# LOAD.net
KiCad netlist of a schematic drawn in Altium Designer
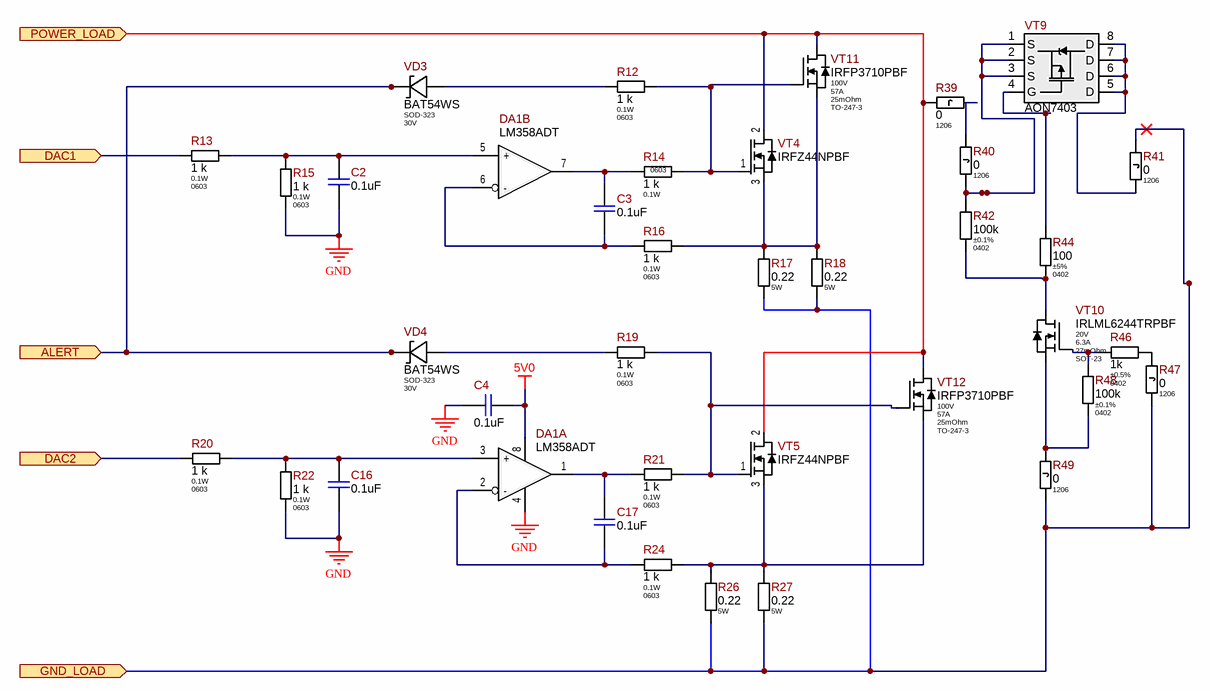
[diagram p0: LOAD.SchDoc]

(export (version "E")
  (design (tool "Eeschema 10.0.6"))
  (components
    (comp (ref "C2")
      (value "0.1uF")
      (footprint "C0603(1608)")
      (description "CAP CER 0.1UF 50V X7R 0603")
      (fields (field (name "PART NUMBER") "0.1uF  50V C0603") (field (name "TOLERANCE") "±10%"))
      (libsource (lib "Database") (part "Capacitor_Ceramic"))
    )
    (comp (ref "C3")
      (value "0.1uF")
      (footprint "C0603(1608)")
      (description "CAP CER 0.1UF 50V X7R 0603")
      (fields (field (name "PART NUMBER") "0.1uF  50V C0603") (field (name "TOLERANCE") "±10%"))
      (libsource (lib "Database") (part "Capacitor_Ceramic"))
    )
    (comp (ref "C4")
      (value "0.1uF")
      (footprint "C0603(1608)")
      (description "CAP CER 0.1UF 50V X7R 0603")
      (fields (field (name "PART NUMBER") "0.1uF  50V C0603") (field (name "TOLERANCE") "±10%"))
      (libsource (lib "Database") (part "Capacitor_Ceramic"))
    )
    (comp (ref "C16")
      (value "0.1uF")
      (footprint "C0603(1608)")
      (description "CAP CER 0.1UF 50V X7R 0603")
      (fields (field (name "PART NUMBER") "0.1uF  50V C0603") (field (name "TOLERANCE") "±10%"))
      (libsource (lib "Database") (part "Capacitor_Ceramic"))
    )
    (comp (ref "C17")
      (value "0.1uF")
      (footprint "C0603(1608)")
      (description "CAP CER 0.1UF 50V X7R 0603")
      (fields (field (name "PART NUMBER") "0.1uF  50V C0603") (field (name "TOLERANCE") "±10%"))
      (libsource (lib "Database") (part "Capacitor_Ceramic"))
    )
    (comp (ref "DA1")
      (value "LM358ADT")
      (footprint "SOIC8")
      (description "IC OPAMP GP 2 CIRCUIT 8SOIC  1.1 MHz   3V...30V")
      (fields (field (name "MANUFACTURER") "Texas Instruments"))
      (libsource (lib "Database") (part "AMP8"))
    )
    (comp (ref "R12")
      (value "1 k")
      (footprint "R0603")
      (description "RES SMD 1 k OHM  ±1% 1/10W 0603")
      (fields
        (field (name "POWER RATING") "0.1W")
        (field (name "PACKAGE/CASE") "0603")
        (field (name "PART NUMBER") "1 k  R0603")
        (field (name "TOLERANCE") "±1%")
      )
      (libsource (lib "Database") (part "R0603"))
    )
    (comp (ref "R13")
      (value "1 k")
      (footprint "R0603")
      (description "RES SMD 1 k OHM  ±1% 1/10W 0603")
      (fields
        (field (name "POWER RATING") "0.1W")
        (field (name "PACKAGE/CASE") "0603")
        (field (name "PART NUMBER") "1 k  R0603")
        (field (name "TOLERANCE") "±1%")
      )
      (libsource (lib "Database") (part "R0603"))
    )
    (comp (ref "R14")
      (value "1 k")
      (footprint "R0603")
      (description "RES SMD 1 k OHM  ±1% 1/10W 0603")
      (fields
        (field (name "POWER RATING") "0.1W")
        (field (name "PACKAGE/CASE") "0603")
        (field (name "PART NUMBER") "1 k  R0603")
        (field (name "TOLERANCE") "±1%")
      )
      (libsource (lib "Database") (part "R0603"))
    )
    (comp (ref "R15")
      (value "1 k")
      (footprint "R0603")
      (description "RES SMD 1 k OHM  ±1% 1/10W 0603")
      (fields
        (field (name "POWER RATING") "0.1W")
        (field (name "PACKAGE/CASE") "0603")
        (field (name "PART NUMBER") "1 k  R0603")
        (field (name "TOLERANCE") "±1%")
      )
      (libsource (lib "Database") (part "R0603"))
    )
    (comp (ref "R16")
      (value "1 k")
      (footprint "R0603")
      (description "RES SMD 1 k OHM  ±1% 1/10W 0603")
      (fields
        (field (name "POWER RATING") "0.1W")
        (field (name "PACKAGE/CASE") "0603")
        (field (name "PART NUMBER") "1 k  R0603")
        (field (name "TOLERANCE") "±1%")
      )
      (libsource (lib "Database") (part "R0603"))
    )
    (comp (ref "R17")
      (value "0.22")
      (footprint "R5W")
      (description "Resistror 47 OHM  ±10% AXIAL  9.00mm x 22.00mm")
      (fields
        (field (name "POWER RATING") "5W")
        (field (name "PART NUMBER") "47  RES_5W")
        (field (name "TOLERANCE") "±10%")
      )
      (libsource (lib "Database") (part "RES_5W"))
    )
    (comp (ref "R18")
      (value "0.22")
      (footprint "R5W")
      (description "Resistror 47 OHM  ±10% AXIAL  9.00mm x 22.00mm")
      (fields
        (field (name "POWER RATING") "5W")
        (field (name "PART NUMBER") "47  RES_5W")
        (field (name "TOLERANCE") "±10%")
      )
      (libsource (lib "Database") (part "RES_5W"))
    )
    (comp (ref "R19")
      (value "1 k")
      (footprint "R0603")
      (description "RES SMD 1 k OHM  ±1% 1/10W 0603")
      (fields
        (field (name "POWER RATING") "0.1W")
        (field (name "PACKAGE/CASE") "0603")
        (field (name "PART NUMBER") "1 k  R0603")
        (field (name "TOLERANCE") "±1%")
      )
      (libsource (lib "Database") (part "R0603"))
    )
    (comp (ref "R20")
      (value "1 k")
      (footprint "R0603")
      (description "RES SMD 1 k OHM  ±1% 1/10W 0603")
      (fields
        (field (name "POWER RATING") "0.1W")
        (field (name "PACKAGE/CASE") "0603")
        (field (name "PART NUMBER") "1 k  R0603")
        (field (name "TOLERANCE") "±1%")
      )
      (libsource (lib "Database") (part "R0603"))
    )
    (comp (ref "R21")
      (value "1 k")
      (footprint "R0603")
      (description "RES SMD 1 k OHM  ±1% 1/10W 0603")
      (fields
        (field (name "POWER RATING") "0.1W")
        (field (name "PACKAGE/CASE") "0603")
        (field (name "PART NUMBER") "1 k  R0603")
        (field (name "TOLERANCE") "±1%")
      )
      (libsource (lib "Database") (part "R0603"))
    )
    (comp (ref "R22")
      (value "1 k")
      (footprint "R0603")
      (description "RES SMD 1 k OHM  ±1% 1/10W 0603")
      (fields
        (field (name "POWER RATING") "0.1W")
        (field (name "PACKAGE/CASE") "0603")
        (field (name "PART NUMBER") "1 k  R0603")
        (field (name "TOLERANCE") "±1%")
      )
      (libsource (lib "Database") (part "R0603"))
    )
    (comp (ref "R24")
      (value "1 k")
      (footprint "R0603")
      (description "RES SMD 1 k OHM  ±1% 1/10W 0603")
      (fields
        (field (name "POWER RATING") "0.1W")
        (field (name "PACKAGE/CASE") "0603")
        (field (name "PART NUMBER") "1 k  R0603")
        (field (name "TOLERANCE") "±1%")
      )
      (libsource (lib "Database") (part "R0603"))
    )
    (comp (ref "R26")
      (value "0.22")
      (footprint "R5W")
      (description "Resistror 47 OHM  ±10% AXIAL  9.00mm x 22.00mm")
      (fields
        (field (name "POWER RATING") "5W")
        (field (name "PART NUMBER") "47  RES_5W")
        (field (name "TOLERANCE") "±10%")
      )
      (libsource (lib "Database") (part "RES_5W"))
    )
    (comp (ref "R27")
      (value "0.22")
      (footprint "R5W")
      (description "Resistror 47 OHM  ±10% AXIAL  9.00mm x 22.00mm")
      (fields
        (field (name "POWER RATING") "5W")
        (field (name "PART NUMBER") "47  RES_5W")
        (field (name "TOLERANCE") "±10%")
      )
      (libsource (lib "Database") (part "RES_5W"))
    )
    (comp (ref "R39")
      (value "0")
      (footprint "R_ANY_CHIP_1206_MED")
      (description "0 Ohms Jumper, 1/2W 1206 Thick Film Resistor")
      (fields
        (field (name "TOLERANCE") "0.5%")
        (field (name "PACKAGE") "1206")
        (field (name "PART NUMBER") "RCS12060000Z0EA")
      )
      (libsource (lib "AjaxLibrary") (part "Resistor-J"))
    )
    (comp (ref "R40")
      (value "0")
      (footprint "R_ANY_CHIP_1206_MED")
      (description "0 Ohms Jumper, 1/2W 1206 Thick Film Resistor")
      (fields
        (field (name "TOLERANCE") "0.5%")
        (field (name "PACKAGE") "1206")
        (field (name "PART NUMBER") "RCS12060000Z0EA")
      )
      (libsource (lib "AjaxLibrary") (part "Resistor-J"))
    )
    (comp (ref "R41")
      (value "0")
      (footprint "R_ANY_CHIP_1206_MED")
      (description "0 Ohms Jumper, 1/2W 1206 Thick Film Resistor")
      (fields
        (field (name "TOLERANCE") "0.5%")
        (field (name "PACKAGE") "1206")
        (field (name "PART NUMBER") "RCS12060000Z0EA")
      )
      (libsource (lib "AjaxLibrary") (part "Resistor-J"))
    )
    (comp (ref "R42")
      (value "100k")
      (footprint "R_ANY_CHIP_0402_MED")
      (description "100 kOhms ±0.1%, 1/16W 0402 Thin Film Resistor")
      (fields
        (field (name "TOLERANCE") "±0.1%")
        (field (name "PACKAGE") "0402")
        (field (name "PART NUMBER") "WF04U1003BTL")
        (field (name "MANUFACTURER") "Walsin Technology Corporation")
      )
      (libsource (lib "AjaxLibrary") (part "Resistor"))
    )
    (comp (ref "R44")
      (value "100")
      (footprint "R_ANY_CHIP_0402_MED")
      (description "100 Ohms ±5% 1/16W 0402 Thick Film Resistor")
      (fields
        (field (name "TOLERANCE") "±5%")
        (field (name "PACKAGE") "0402")
        (field (name "PART NUMBER") "RC0402JR-07100RL")
        (field (name "MANUFACTURER") "Yageo")
      )
      (libsource (lib "AjaxLibrary") (part "Resistor"))
    )
    (comp (ref "R46")
      (value "1k")
      (footprint "R_ANY_CHIP_0402_MED")
      (description "1 kOhms ±0.5% 1/16W 0402 Thick Film Resistor")
      (fields
        (field (name "TOLERANCE") "±0.5%")
        (field (name "PACKAGE") "0402")
        (field (name "PART NUMBER") "RC0402DR-071KL")
        (field (name "MANUFACTURER") "Yageo")
      )
      (libsource (lib "AjaxLibrary") (part "Resistor"))
    )
    (comp (ref "R47")
      (value "0")
      (footprint "R_ANY_CHIP_1206_MED")
      (description "0 Ohms Jumper, 1/2W 1206 Thick Film Resistor")
      (fields
        (field (name "TOLERANCE") "0.5%")
        (field (name "PACKAGE") "1206")
        (field (name "PART NUMBER") "RCS12060000Z0EA")
      )
      (libsource (lib "AjaxLibrary") (part "Resistor-J"))
    )
    (comp (ref "R48")
      (value "100k")
      (footprint "R_ANY_CHIP_0402_MED")
      (description "100 kOhms ±0.1%, 1/16W 0402 Thin Film Resistor")
      (fields
        (field (name "TOLERANCE") "±0.1%")
        (field (name "PACKAGE") "0402")
        (field (name "PART NUMBER") "WF04U1003BTL")
        (field (name "MANUFACTURER") "Walsin Technology Corporation")
      )
      (libsource (lib "AjaxLibrary") (part "Resistor"))
    )
    (comp (ref "R49")
      (value "0")
      (footprint "R_ANY_CHIP_1206_MED")
      (description "0 Ohms Jumper, 1/2W 1206 Thick Film Resistor")
      (fields
        (field (name "TOLERANCE") "0.5%")
        (field (name "PACKAGE") "1206")
        (field (name "PART NUMBER") "RCS12060000Z0EA")
      )
      (libsource (lib "AjaxLibrary") (part "Resistor-J"))
    )
    (comp (ref "VD3")
      (value "BAT54WS")
      (footprint "SOD-323_MED")
      (description "Diode Schottky 30V 100mA, Fast Recovery 5ns, Low Leakage 2uA, SOD-323")
      (fields
        (field (name "PART NUMBER") "BAT54WS-7-F")
        (field (name "MANUFACTURER") "Diodes Incorporated")
        (field (name "PACKAGE") "SOD-323")
        (field (name "VOLTAGE") "30V")
      )
      (libsource (lib "AjaxLibrary") (part "Diode-Schottky"))
    )
    (comp (ref "VD4")
      (value "BAT54WS")
      (footprint "SOD-323_MED")
      (description "Diode Schottky 30V 100mA, Fast Recovery 5ns, Low Leakage 2uA, SOD-323")
      (fields
        (field (name "PART NUMBER") "BAT54WS-7-F")
        (field (name "MANUFACTURER") "Diodes Incorporated")
        (field (name "PACKAGE") "SOD-323")
        (field (name "VOLTAGE") "30V")
      )
      (libsource (lib "AjaxLibrary") (part "Diode-Schottky"))
    )
    (comp (ref "VT4")
      (value "IRFZ44NPBF")
      (footprint "TO-220")
      (description "MOSFET N-CH 55V 49A TO220AB")
      (fields (field (name "MANUFACTURER") "Infineon Technologies"))
      (libsource (lib "Database") (part "IRFZ44"))
    )
    (comp (ref "VT5")
      (value "IRFZ44NPBF")
      (footprint "TO-220")
      (description "MOSFET N-CH 55V 49A TO220AB")
      (fields (field (name "MANUFACTURER") "Infineon Technologies"))
      (libsource (lib "Database") (part "IRFZ44"))
    )
    (comp (ref "VT9")
      (value "AON7403")
      (footprint "DFN3X3")
      (description "P-Channel 30 V 11A (Ta), 29A (Tc) 3.1W (Ta), 25W (Tc) Surface Mount 8-DFN-EP (3x3)")
      (fields
        (field (name "PART NUMBER") "AON7403")
        (field (name "MANUFACTURER") "Alpha & Omega Semiconductor Inc.")
      )
      (libsource (lib "Database") (part "AON7403"))
    )
    (comp (ref "VT10")
      (value "IRLML6244")
      (footprint "SOT-23_MED")
      (description "20V, 6.3A max N-Channel HEXFET MOSFET, 21mOhm @ Vgs = 4.5V")
      (fields
        (field (name "PART NUMBER") "IRLML6244TRPBF")
        (field (name "VDS") "20V")
        (field (name "ID") "6.3A")
        (field (name "RDS") "27mOhm")
        (field (name "PACKAGE") "SOT-23")
        (field (name "MANUFACTURER") "Infineon Technologies")
      )
      (libsource (lib "AjaxLibrary") (part "MOSFET-N-Channel"))
    )
    (comp (ref "VT11")
      (value "IRFP3710PBF")
      (footprint "TO-247-3")
      (description "100V, 57A max N-Channel HEXFET Power MOSFET, 25mOhm @ Vgs = 10V")
      (fields
        (field (name "PART NUMBER") "IRFP3710PBF")
        (field (name "VDS") "100V")
        (field (name "ID") "57A")
        (field (name "RDS") "25mOhm")
        (field (name "PACKAGE") "TO-247-3")
        (field (name "MANUFACTURER") "Infineon Technologies")
      )
      (libsource (lib "AjaxLibrary") (part "MOSFET-N-Channel-(TO-247)"))
    )
    (comp (ref "VT12")
      (value "IRFP3710PBF")
      (footprint "TO-247-3")
      (description "100V, 57A max N-Channel HEXFET Power MOSFET, 25mOhm @ Vgs = 10V")
      (fields
        (field (name "PART NUMBER") "IRFP3710PBF")
        (field (name "VDS") "100V")
        (field (name "ID") "57A")
        (field (name "RDS") "25mOhm")
        (field (name "PACKAGE") "TO-247-3")
        (field (name "MANUFACTURER") "Infineon Technologies")
      )
      (libsource (lib "AjaxLibrary") (part "MOSFET-N-Channel-(TO-247)"))
    )
  )
  (nets
    (net (code "1") (name "/ALERT") (class "Default")
      (node (ref "VD3") (pin "CA") (pintype "passive"))
      (node (ref "VD4") (pin "CA") (pintype "passive"))
    )
    (net (code "2") (name "/DAC1") (class "Default")
      (node (ref "R13") (pin "1") (pinfunction "1_1") (pintype "passive"))
    )
    (net (code "3") (name "/DAC2") (class "Default")
      (node (ref "R20") (pin "1") (pinfunction "1_1") (pintype "passive"))
    )
    (net (code "4") (name "/GND_LOAD") (class "Default")
      (node (ref "R17") (pin "1") (pinfunction "1_1") (pintype "passive"))
      (node (ref "R18") (pin "1") (pinfunction "1_1") (pintype "passive"))
      (node (ref "R26") (pin "1") (pinfunction "1_1") (pintype "passive"))
      (node (ref "R27") (pin "1") (pinfunction "1_1") (pintype "passive"))
      (node (ref "R41") (pin "1") (pintype "passive"))
      (node (ref "R47") (pin "2") (pintype "passive"))
      (node (ref "R49") (pin "2") (pintype "passive"))
    )
    (net (code "5") (name "/POWER_LOAD") (class "Default")
      (node (ref "R39") (pin "1") (pintype "passive"))
      (node (ref "VT11") (pin "2") (pinfunction "D_2") (pintype "passive"))
      (node (ref "VT12") (pin "2") (pinfunction "D_2") (pintype "passive"))
      (node (ref "VT4") (pin "2") (pinfunction "D_2") (pintype "passive"))
      (node (ref "VT5") (pin "2") (pinfunction "D_2") (pintype "passive"))
    )
    (net (code "6") (name "5V0") (class "Default")
      (node (ref "C4") (pin "1") (pinfunction "1_1") (pintype "passive"))
      (node (ref "DA1") (pin "8") (pinfunction "V+_8") (pintype "passive"))
    )
    (net (code "7") (name "GND") (class "Default")
      (node (ref "C16") (pin "2") (pinfunction "2_2") (pintype "passive"))
      (node (ref "C2") (pin "2") (pinfunction "2_2") (pintype "passive"))
      (node (ref "C4") (pin "2") (pinfunction "2_2") (pintype "passive"))
      (node (ref "DA1") (pin "4") (pinfunction "V-_4") (pintype "passive"))
      (node (ref "R15") (pin "1") (pinfunction "1_1") (pintype "passive"))
      (node (ref "R22") (pin "1") (pinfunction "1_1") (pintype "passive"))
    )
    (net (code "8") (name "Net-(DA1A-+)") (class "Default")
      (node (ref "C16") (pin "1") (pinfunction "1_1") (pintype "passive"))
      (node (ref "DA1") (pin "3") (pinfunction "+_3") (pintype "passive"))
      (node (ref "R20") (pin "2") (pinfunction "2_2") (pintype "passive"))
      (node (ref "R22") (pin "2") (pinfunction "2_2") (pintype "passive"))
    )
    (net (code "9") (name "Net-(DA1A--)") (class "Default")
      (node (ref "C17") (pin "2") (pinfunction "2_2") (pintype "passive"))
      (node (ref "DA1") (pin "2") (pinfunction "-_2") (pintype "passive"))
      (node (ref "R24") (pin "1") (pinfunction "1_1") (pintype "passive"))
    )
    (net (code "10") (name "Net-(DA1A-Out)") (class "Default")
      (node (ref "C17") (pin "1") (pinfunction "1_1") (pintype "passive"))
      (node (ref "DA1") (pin "1") (pinfunction "Out_1") (pintype "passive"))
      (node (ref "R21") (pin "1") (pinfunction "1_1") (pintype "passive"))
    )
    (net (code "11") (name "Net-(DA1B-+)") (class "Default")
      (node (ref "C2") (pin "1") (pinfunction "1_1") (pintype "passive"))
      (node (ref "DA1") (pin "5") (pinfunction "+_5") (pintype "passive"))
      (node (ref "R13") (pin "2") (pinfunction "2_2") (pintype "passive"))
      (node (ref "R15") (pin "2") (pinfunction "2_2") (pintype "passive"))
    )
    (net (code "12") (name "Net-(DA1B--)") (class "Default")
      (node (ref "C3") (pin "2") (pinfunction "2_2") (pintype "passive"))
      (node (ref "DA1") (pin "6") (pinfunction "-_6") (pintype "passive"))
      (node (ref "R16") (pin "1") (pinfunction "1_1") (pintype "passive"))
    )
    (net (code "13") (name "Net-(DA1B-Out)") (class "Default")
      (node (ref "C3") (pin "1") (pinfunction "1_1") (pintype "passive"))
      (node (ref "DA1") (pin "7") (pinfunction "Out_7") (pintype "passive"))
      (node (ref "R14") (pin "1") (pinfunction "1_1") (pintype "passive"))
    )
    (net (code "14") (name "Net-(R12-Pad1)") (class "Default")
      (node (ref "R12") (pin "1") (pinfunction "1_1") (pintype "passive"))
      (node (ref "VD3") (pin "AN") (pintype "passive"))
    )
    (net (code "15") (name "Net-(R19-Pad1)") (class "Default")
      (node (ref "R19") (pin "1") (pinfunction "1_1") (pintype "passive"))
      (node (ref "VD4") (pin "AN") (pintype "passive"))
    )
    (net (code "16") (name "Net-(R39-Pad2)") (class "Default")
      (node (ref "R39") (pin "2") (pintype "passive"))
      (node (ref "R40") (pin "1") (pintype "passive"))
    )
    (net (code "17") (name "Net-(R40-Pad2)") (class "Default")
      (node (ref "R40") (pin "2") (pintype "passive"))
      (node (ref "R42") (pin "1") (pintype "passive"))
      (node (ref "VT9") (pin "1") (pinfunction "S_1") (pintype "passive"))
      (node (ref "VT9") (pin "2") (pinfunction "S_2") (pintype "passive"))
      (node (ref "VT9") (pin "3") (pinfunction "S_3") (pintype "passive"))
    )
    (net (code "18") (name "Net-(R41-Pad2)") (class "Default")
      (node (ref "R41") (pin "2") (pintype "passive"))
      (node (ref "VT9") (pin "5") (pinfunction "D_5") (pintype "passive"))
      (node (ref "VT9") (pin "6") (pinfunction "D_6") (pintype "passive"))
      (node (ref "VT9") (pin "7") (pinfunction "D_7") (pintype "passive"))
      (node (ref "VT9") (pin "8") (pinfunction "D_8") (pintype "passive"))
    )
    (net (code "19") (name "Net-(R46-Pad1)") (class "Default")
      (node (ref "R46") (pin "1") (pintype "passive"))
      (node (ref "R47") (pin "1") (pintype "passive"))
    )
    (net (code "20") (name "Net-(VT9-G)") (class "Default")
      (node (ref "R44") (pin "1") (pintype "passive"))
      (node (ref "VT9") (pin "4") (pinfunction "G_4") (pintype "passive"))
    )
    (net (code "21") (name "Net-(VT10-D)") (class "Default")
      (node (ref "R42") (pin "2") (pintype "passive"))
      (node (ref "R44") (pin "2") (pintype "passive"))
      (node (ref "VT10") (pin "3") (pinfunction "D_3") (pintype "passive"))
    )
    (net (code "22") (name "Net-(VT10-G)") (class "Default")
      (node (ref "R46") (pin "2") (pintype "passive"))
      (node (ref "R48") (pin "1") (pintype "passive"))
      (node (ref "VT10") (pin "1") (pinfunction "G_1") (pintype "passive"))
    )
    (net (code "23") (name "Net-(VT10-S)") (class "Default")
      (node (ref "R48") (pin "2") (pintype "passive"))
      (node (ref "R49") (pin "1") (pintype "passive"))
      (node (ref "VT10") (pin "2") (pinfunction "S_2") (pintype "passive"))
    )
    (net (code "24") (name "Net-(VT11-G)") (class "Default")
      (node (ref "R12") (pin "2") (pinfunction "2_2") (pintype "passive"))
      (node (ref "R14") (pin "2") (pinfunction "2_2") (pintype "passive"))
      (node (ref "VT11") (pin "1") (pinfunction "G_1") (pintype "passive"))
      (node (ref "VT4") (pin "1") (pinfunction "G_1") (pintype "passive"))
    )
    (net (code "25") (name "Net-(VT11-S)") (class "Default")
      (node (ref "R16") (pin "2") (pinfunction "2_2") (pintype "passive"))
      (node (ref "R17") (pin "2") (pinfunction "2_2") (pintype "passive"))
      (node (ref "R18") (pin "2") (pinfunction "2_2") (pintype "passive"))
      (node (ref "VT11") (pin "3") (pinfunction "S_3") (pintype "passive"))
      (node (ref "VT4") (pin "3") (pinfunction "S_3") (pintype "passive"))
    )
    (net (code "26") (name "Net-(VT12-G)") (class "Default")
      (node (ref "R19") (pin "2") (pinfunction "2_2") (pintype "passive"))
      (node (ref "R21") (pin "2") (pinfunction "2_2") (pintype "passive"))
      (node (ref "VT12") (pin "1") (pinfunction "G_1") (pintype "passive"))
      (node (ref "VT5") (pin "1") (pinfunction "G_1") (pintype "passive"))
    )
    (net (code "27") (name "Net-(VT12-S)") (class "Default")
      (node (ref "R24") (pin "2") (pinfunction "2_2") (pintype "passive"))
      (node (ref "R26") (pin "2") (pinfunction "2_2") (pintype "passive"))
      (node (ref "R27") (pin "2") (pinfunction "2_2") (pintype "passive"))
      (node (ref "VT12") (pin "3") (pinfunction "S_3") (pintype "passive"))
      (node (ref "VT5") (pin "3") (pinfunction "S_3") (pintype "passive"))
    )
  )
)
